# Laser_Teensy_proto.net
KiCad netlist of a schematic drawn in EAGLE
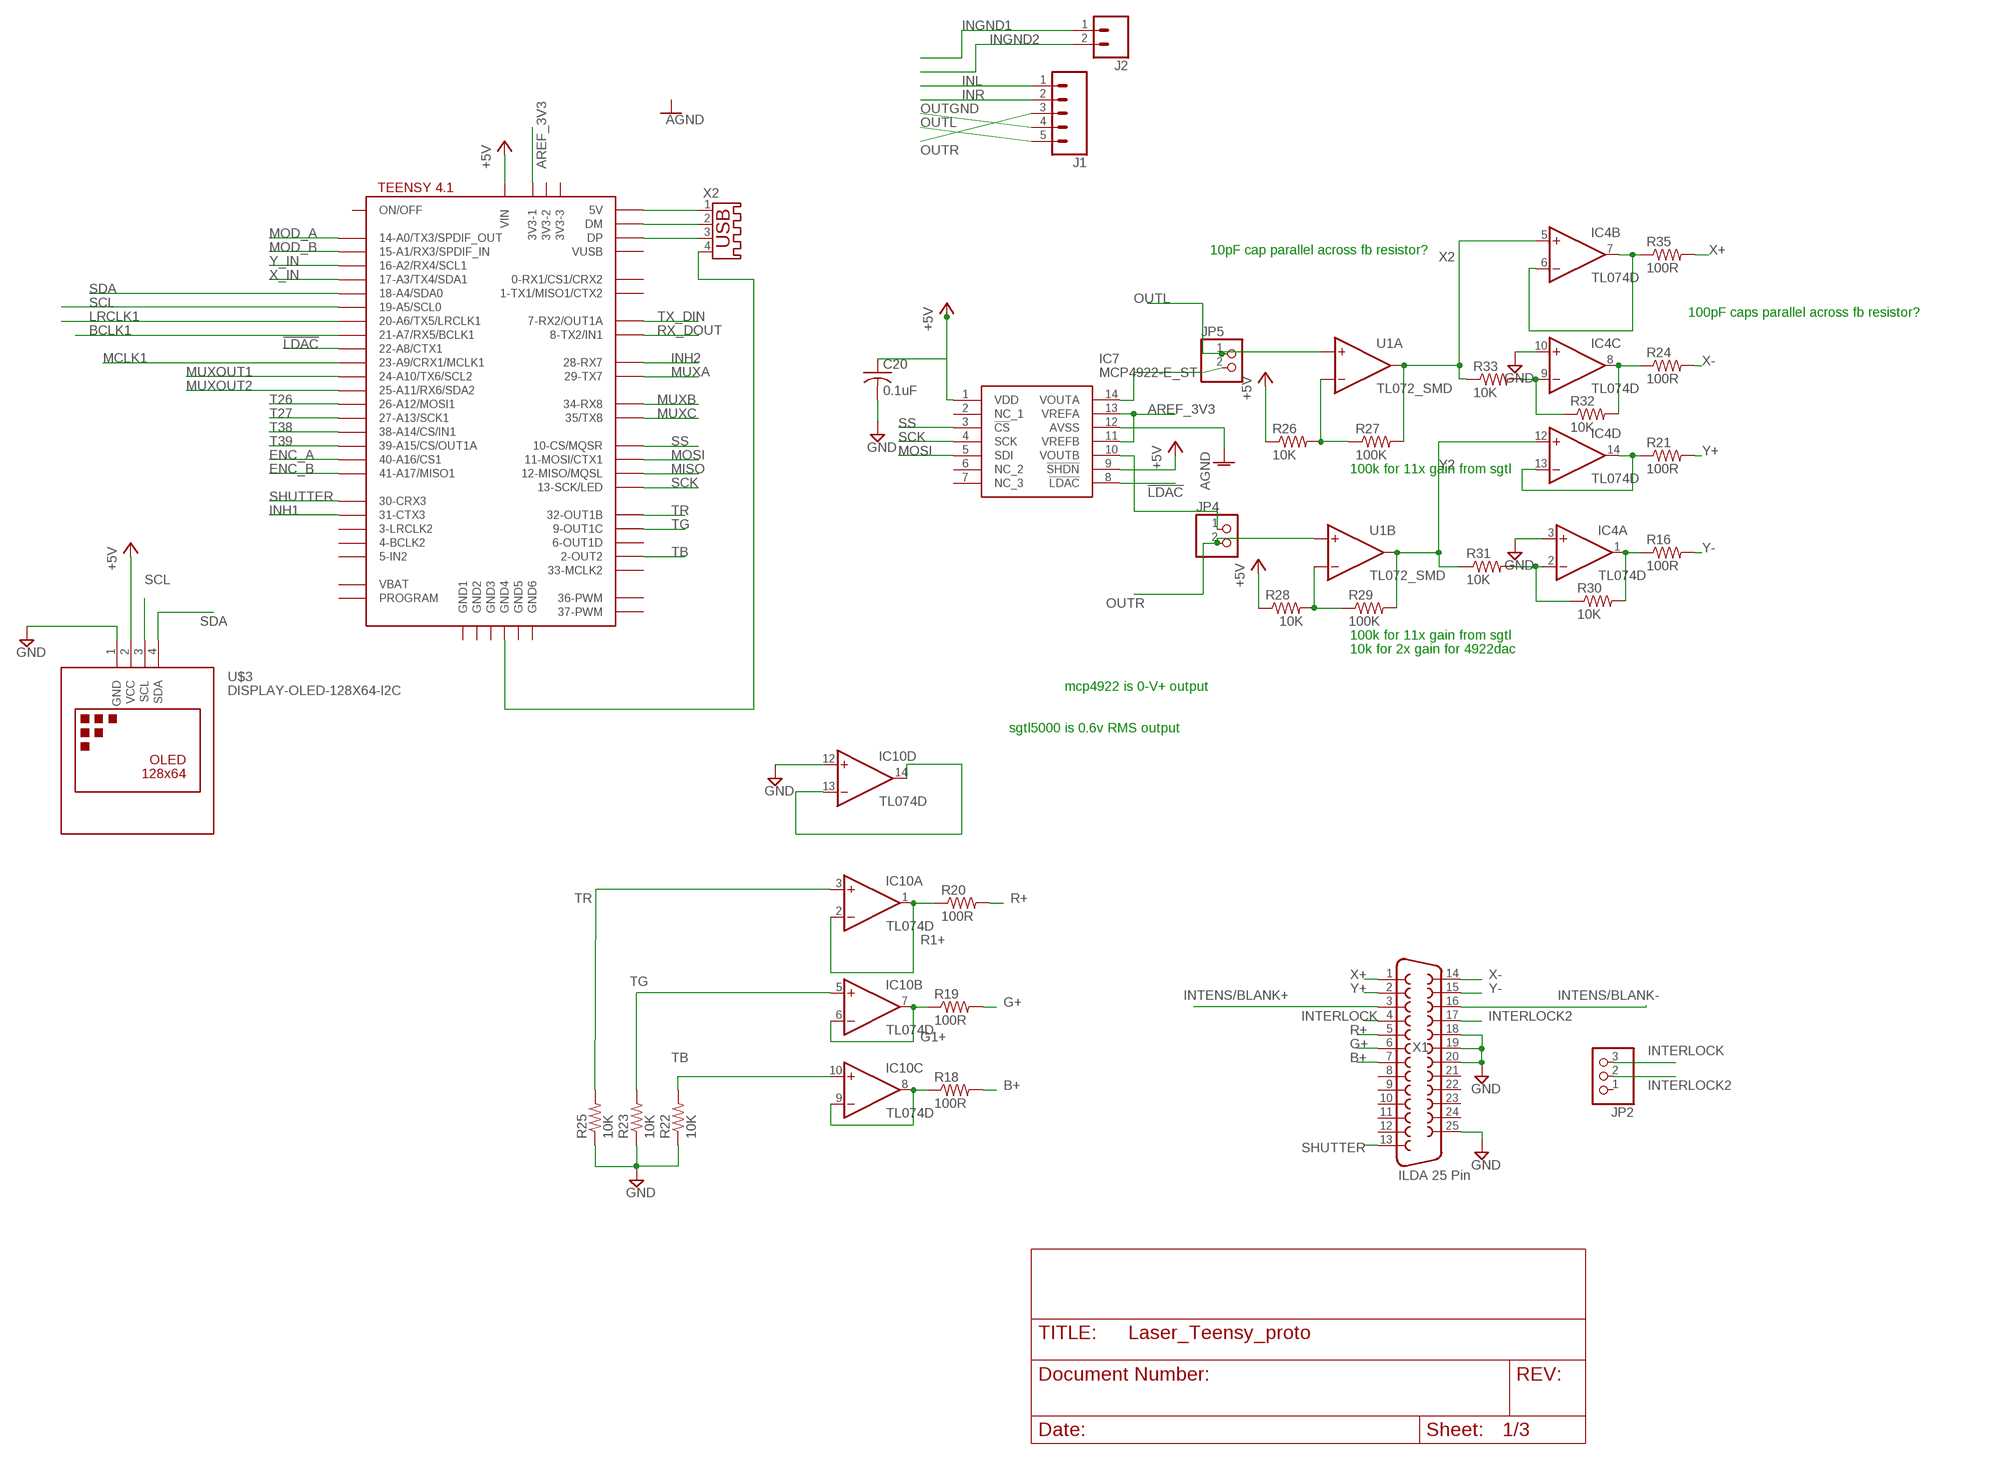
[diagram p0: schematic, sheet 1]
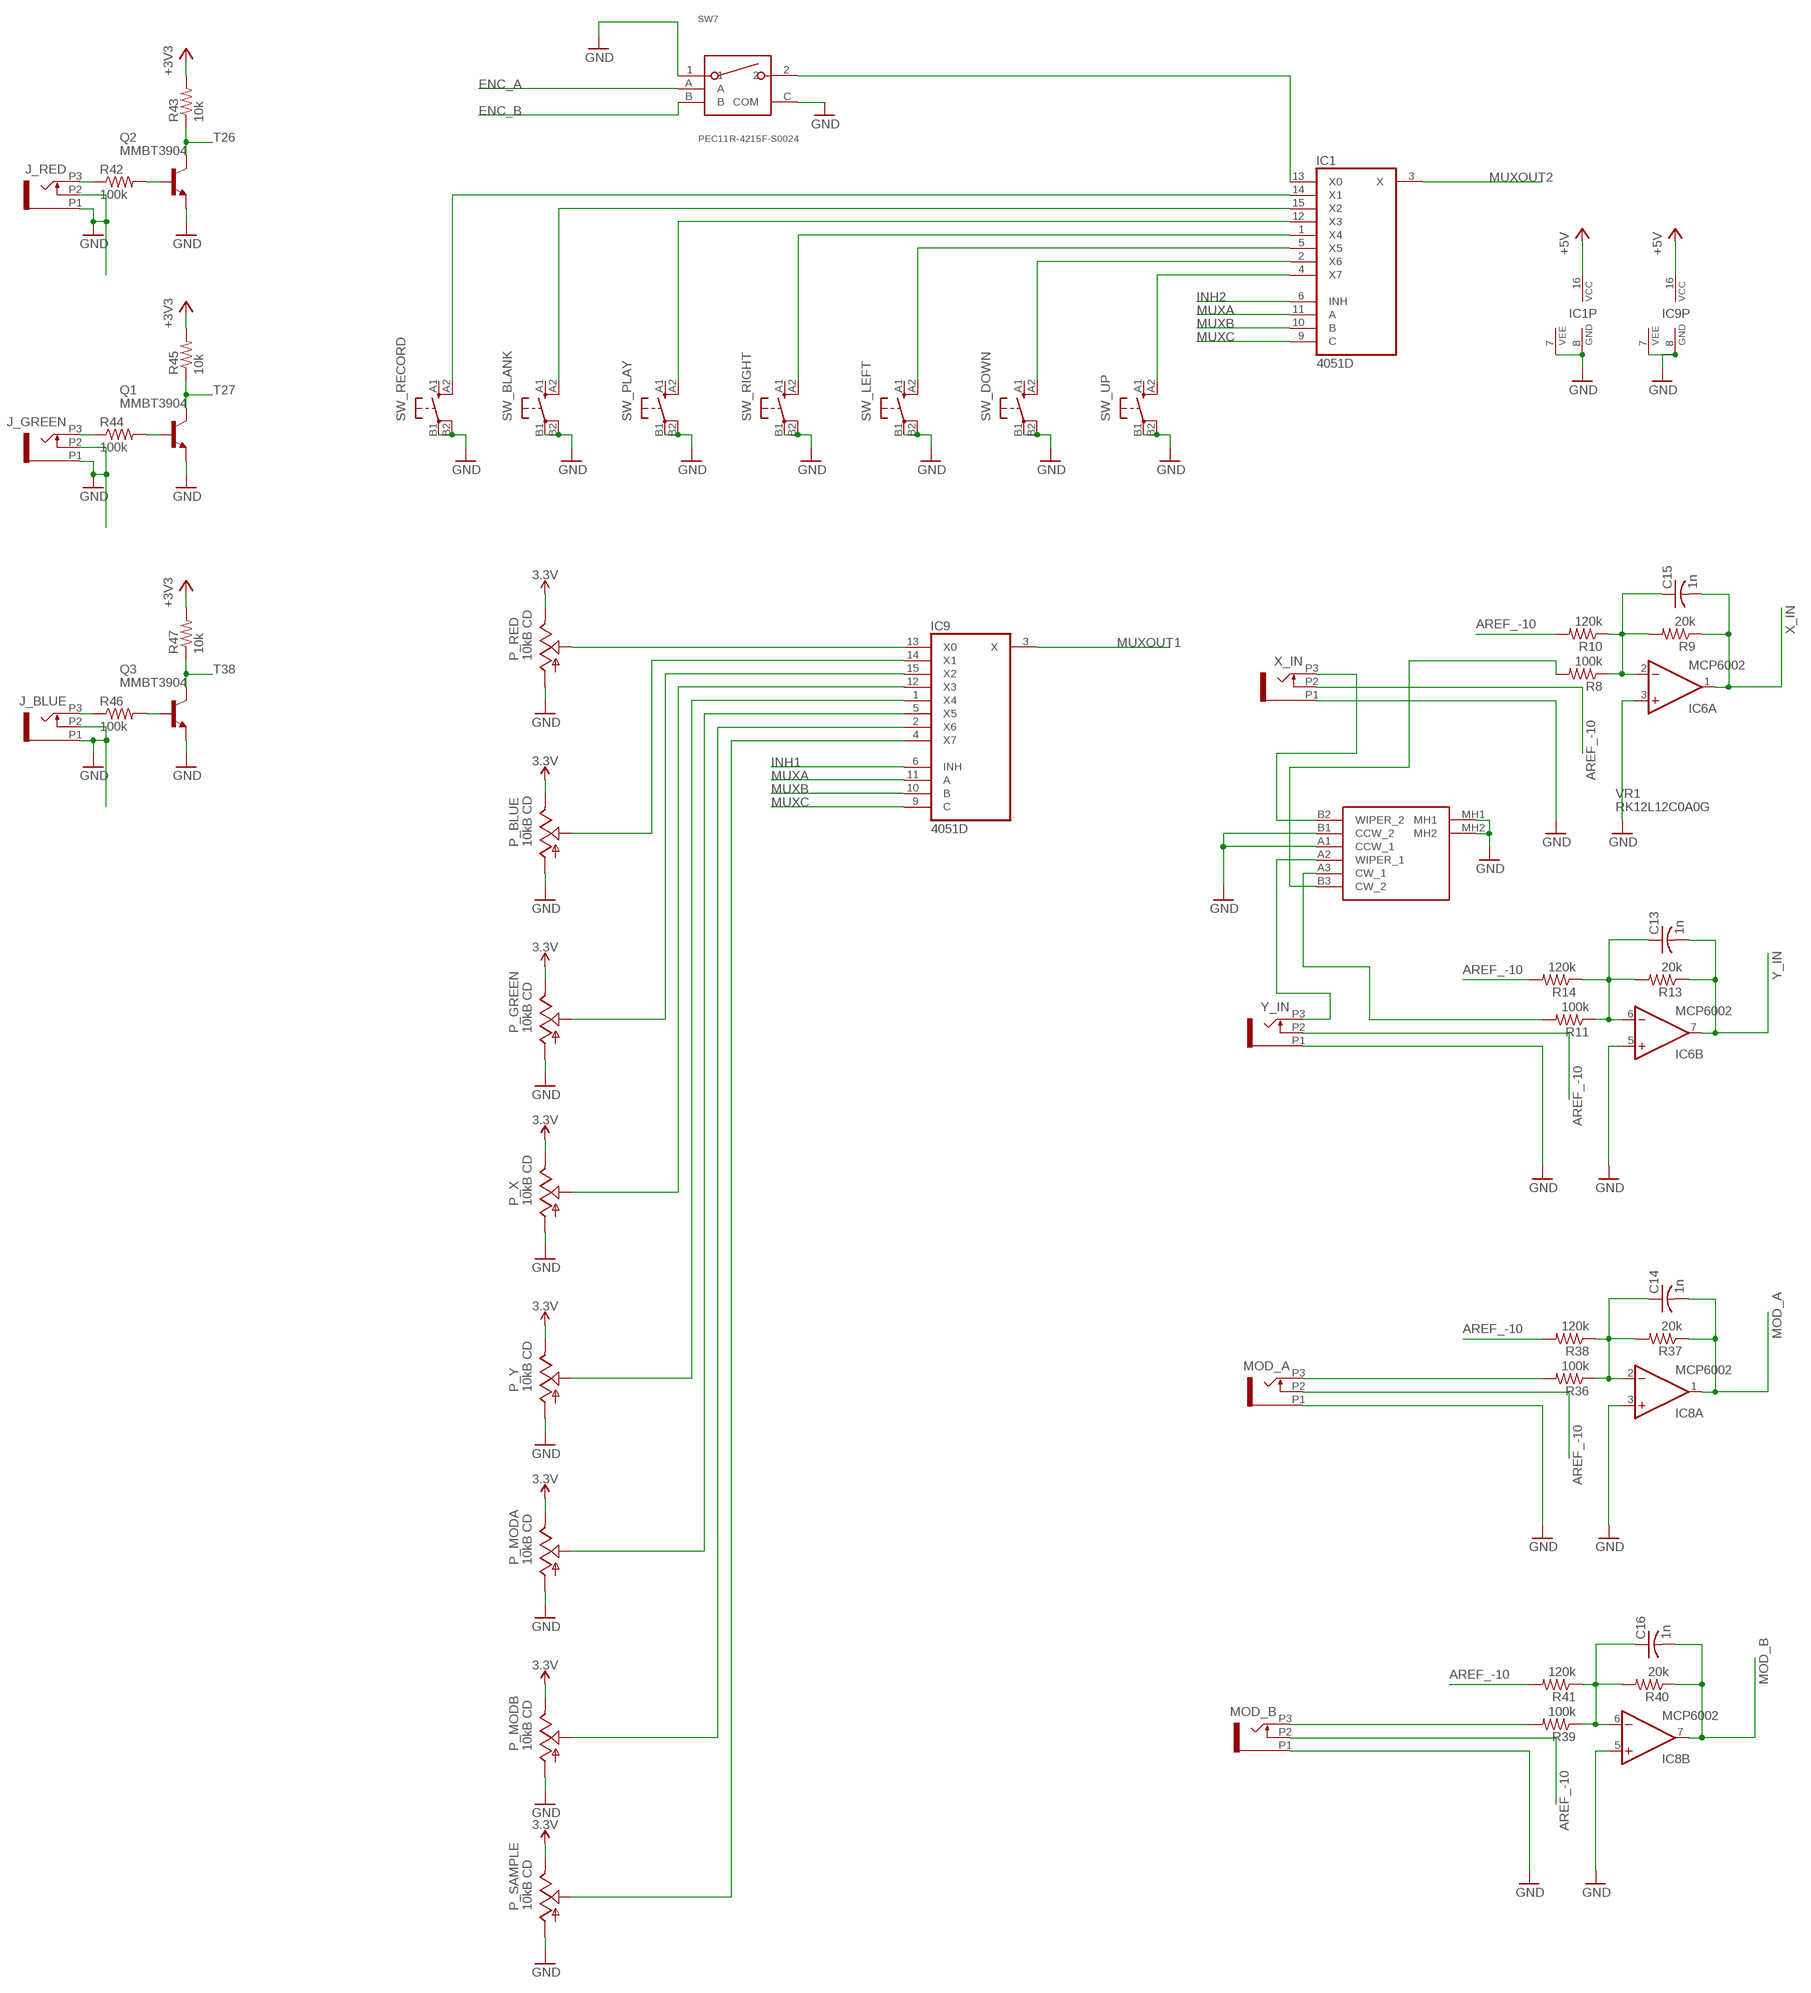
[diagram p1: schematic, sheet 2]
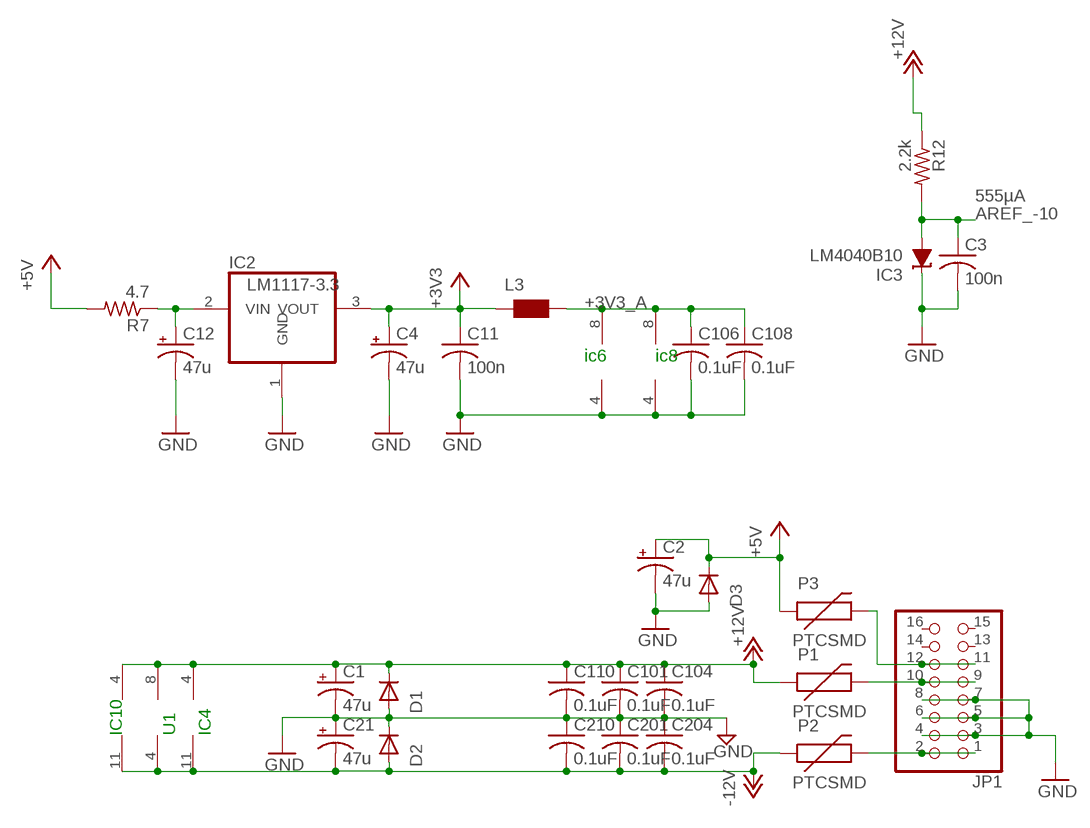
[diagram p2: schematic, sheet 3]

(export (version "E")
  (design (tool "Eeschema 10.0.6"))
  (components
    (comp (ref "C13")
      (value "1n")
      (footprint "eagle-import:C050-025X075")
      (libsource (lib "eagle-import") (part "rcl_334_C-US050-025X075"))
    )
    (comp (ref "C14")
      (value "1n")
      (footprint "eagle-import:C050-025X075")
      (libsource (lib "eagle-import") (part "rcl_334_C-US050-025X075"))
    )
    (comp (ref "C15")
      (value "1n")
      (footprint "eagle-import:C050-025X075")
      (libsource (lib "eagle-import") (part "rcl_334_C-US050-025X075"))
    )
    (comp (ref "C16")
      (value "1n")
      (footprint "eagle-import:C050-025X075")
      (libsource (lib "eagle-import") (part "rcl_334_C-US050-025X075"))
    )
    (comp (ref "IC1")
      (value "4051D")
      (footprint "eagle-import:SO16")
      (libsource (lib "eagle-import") (part "4051D"))
    )
    (comp (ref "IC6")
      (value "MCP6002")
      (footprint "eagle-import:SO08")
      (libsource (lib "eagle-import") (part "TL072D"))
    )
    (comp (ref "IC8")
      (value "MCP6002")
      (footprint "eagle-import:SO08")
      (libsource (lib "eagle-import") (part "TL072D"))
    )
    (comp (ref "IC9")
      (value "4051D")
      (footprint "eagle-import:SO16")
      (libsource (lib "eagle-import") (part "4051D"))
    )
    (comp (ref "J_BLUE")
      (value "PJ301_THONKICONN6")
      (footprint "eagle-import:WQP_PJ_301M6")
      (libsource (lib "eagle-import") (part "PJ301_THONKICONN6"))
    )
    (comp (ref "J_GREEN")
      (value "PJ301_THONKICONN6")
      (footprint "eagle-import:WQP_PJ_301M6")
      (libsource (lib "eagle-import") (part "PJ301_THONKICONN6"))
    )
    (comp (ref "J_RED")
      (value "PJ301_THONKICONN6")
      (footprint "eagle-import:WQP_PJ_301M6")
      (libsource (lib "eagle-import") (part "PJ301_THONKICONN6"))
    )
    (comp (ref "MOD_A")
      (value "PJ301_THONKICONN6")
      (footprint "eagle-import:WQP_PJ_301M6")
      (libsource (lib "eagle-import") (part "og-pj301_variations_PJ301_THONKICONN6"))
    )
    (comp (ref "MOD_B")
      (value "PJ301_THONKICONN6")
      (footprint "eagle-import:WQP_PJ_301M6")
      (libsource (lib "eagle-import") (part "og-pj301_variations_PJ301_THONKICONN6"))
    )
    (comp (ref "P_BLUE")
      (value "10kB CD")
      (footprint "eagle-import:ALPS_POT_VERTICAL_PS")
      (libsource (lib "eagle-import") (part "POT_USVERTICAL_PS"))
    )
    (comp (ref "P_GREEN")
      (value "10kB CD")
      (footprint "eagle-import:ALPS_POT_VERTICAL_PS")
      (libsource (lib "eagle-import") (part "POT_USVERTICAL_PS"))
    )
    (comp (ref "P_MODA")
      (value "10kB CD")
      (footprint "eagle-import:ALPS_POT_VERTICAL_PS")
      (libsource (lib "eagle-import") (part "POT_USVERTICAL_PS"))
    )
    (comp (ref "P_MODB")
      (value "10kB CD")
      (footprint "eagle-import:ALPS_POT_VERTICAL_PS")
      (libsource (lib "eagle-import") (part "POT_USVERTICAL_PS"))
    )
    (comp (ref "P_RED")
      (value "10kB CD")
      (footprint "eagle-import:ALPS_POT_VERTICAL_PS")
      (libsource (lib "eagle-import") (part "POT_USVERTICAL_PS"))
    )
    (comp (ref "P_SAMPLE")
      (value "10kB CD")
      (footprint "eagle-import:ALPS_POT_VERTICAL_PS")
      (libsource (lib "eagle-import") (part "POT_USVERTICAL_PS"))
    )
    (comp (ref "P_X")
      (value "10kB CD")
      (footprint "eagle-import:ALPS_POT_VERTICAL_PS")
      (libsource (lib "eagle-import") (part "POT_USVERTICAL_PS"))
    )
    (comp (ref "P_Y")
      (value "10kB CD")
      (footprint "eagle-import:ALPS_POT_VERTICAL_PS")
      (libsource (lib "eagle-import") (part "POT_USVERTICAL_PS"))
    )
    (comp (ref "Q1")
      (value "MMBT3904")
      (footprint "eagle-import:SOT23-BEC")
      (libsource (lib "eagle-import") (part "-NPN-SOT23-BECMMBT3904LT1"))
    )
    (comp (ref "Q2")
      (value "MMBT3904")
      (footprint "eagle-import:SOT23-BEC")
      (libsource (lib "eagle-import") (part "-NPN-SOT23-BECMMBT3904LT1"))
    )
    (comp (ref "Q3")
      (value "MMBT3904")
      (footprint "eagle-import:SOT23-BEC")
      (libsource (lib "eagle-import") (part "-NPN-SOT23-BECMMBT3904LT1"))
    )
    (comp (ref "R8")
      (value "100k")
      (footprint "eagle-import:0204_5")
      (libsource (lib "eagle-import") (part "rcl_334_R-US_0204/5"))
    )
    (comp (ref "R9")
      (value "20k")
      (footprint "eagle-import:0204_5")
      (libsource (lib "eagle-import") (part "rcl_334_R-US_0204/5"))
    )
    (comp (ref "R10")
      (value "120k")
      (footprint "eagle-import:0204_5")
      (libsource (lib "eagle-import") (part "rcl_334_R-US_0204/5"))
    )
    (comp (ref "R11")
      (value "100k")
      (footprint "eagle-import:0204_5")
      (libsource (lib "eagle-import") (part "rcl_334_R-US_0204/5"))
    )
    (comp (ref "R13")
      (value "20k")
      (footprint "eagle-import:0204_5")
      (libsource (lib "eagle-import") (part "rcl_334_R-US_0204/5"))
    )
    (comp (ref "R14")
      (value "120k")
      (footprint "eagle-import:0204_5")
      (libsource (lib "eagle-import") (part "rcl_334_R-US_0204/5"))
    )
    (comp (ref "R36")
      (value "100k")
      (footprint "eagle-import:0204_5")
      (libsource (lib "eagle-import") (part "rcl_334_R-US_0204/5"))
    )
    (comp (ref "R37")
      (value "20k")
      (footprint "eagle-import:0204_5")
      (libsource (lib "eagle-import") (part "rcl_334_R-US_0204/5"))
    )
    (comp (ref "R38")
      (value "120k")
      (footprint "eagle-import:0204_5")
      (libsource (lib "eagle-import") (part "rcl_334_R-US_0204/5"))
    )
    (comp (ref "R39")
      (value "100k")
      (footprint "eagle-import:0204_5")
      (libsource (lib "eagle-import") (part "rcl_334_R-US_0204/5"))
    )
    (comp (ref "R40")
      (value "20k")
      (footprint "eagle-import:0204_5")
      (libsource (lib "eagle-import") (part "rcl_334_R-US_0204/5"))
    )
    (comp (ref "R41")
      (value "120k")
      (footprint "eagle-import:0204_5")
      (libsource (lib "eagle-import") (part "rcl_334_R-US_0204/5"))
    )
    (comp (ref "R42")
      (value "100k")
      (footprint "eagle-import:0204_5")
      (libsource (lib "eagle-import") (part "rcl_334_R-US_0204/5"))
    )
    (comp (ref "R43")
      (value "10k")
      (footprint "eagle-import:0204_5")
      (libsource (lib "eagle-import") (part "rcl_334_R-US_0204/5"))
    )
    (comp (ref "R44")
      (value "100k")
      (footprint "eagle-import:0204_5")
      (libsource (lib "eagle-import") (part "rcl_334_R-US_0204/5"))
    )
    (comp (ref "R45")
      (value "10k")
      (footprint "eagle-import:0204_5")
      (libsource (lib "eagle-import") (part "rcl_334_R-US_0204/5"))
    )
    (comp (ref "R46")
      (value "100k")
      (footprint "eagle-import:0204_5")
      (libsource (lib "eagle-import") (part "rcl_334_R-US_0204/5"))
    )
    (comp (ref "R47")
      (value "10k")
      (footprint "eagle-import:0204_5")
      (libsource (lib "eagle-import") (part "rcl_334_R-US_0204/5"))
    )
    (comp (ref "SW7")
      (value "PEC11R-4215F-S0024")
      (footprint "eagle-import:PEC11R-4215F-S0024")
      (fields
        (field (name "DIGIKEY_PART_NUMBER") "PEC11R-4215F-S0024-ND")
        (field (name "MANUFACTURER") "Bourns Inc.")
        (field (name "CREATED_BY") "PCBLayout.com")
      )
      (libsource (lib "eagle-import") (part "PEC11R-4215F-S0024"))
    )
    (comp (ref "SW_BLANK")
      (value "D6R")
      (footprint "eagle-import:D6R")
      (libsource (lib "eagle-import") (part "D6R"))
    )
    (comp (ref "SW_DOWN")
      (value "D6R")
      (footprint "eagle-import:D6R")
      (libsource (lib "eagle-import") (part "D6R"))
    )
    (comp (ref "SW_LEFT")
      (value "D6R")
      (footprint "eagle-import:D6R")
      (libsource (lib "eagle-import") (part "D6R"))
    )
    (comp (ref "SW_PLAY")
      (value "D6R")
      (footprint "eagle-import:D6R")
      (libsource (lib "eagle-import") (part "D6R"))
    )
    (comp (ref "SW_RECORD")
      (value "D6R")
      (footprint "eagle-import:D6R")
      (libsource (lib "eagle-import") (part "D6R"))
    )
    (comp (ref "SW_RIGHT")
      (value "D6R")
      (footprint "eagle-import:D6R")
      (libsource (lib "eagle-import") (part "D6R"))
    )
    (comp (ref "SW_UP")
      (value "D6R")
      (footprint "eagle-import:D6R")
      (libsource (lib "eagle-import") (part "D6R"))
    )
    (comp (ref "VR1")
      (value "RK12L12C0A0G")
      (footprint "eagle-import:RK12L12C0A0G")
      (fields (field (name "MOUSER_PART_NUMBER") "688-RK12L12C0A0G"))
      (libsource (lib "eagle-import") (part "RK12L12C0A0G"))
    )
    (comp (ref "X_IN")
      (value "PJ301_THONKICONN6")
      (footprint "eagle-import:WQP_PJ_301M6")
      (libsource (lib "eagle-import") (part "og-pj301_variations_PJ301_THONKICONN6"))
    )
    (comp (ref "Y_IN")
      (value "PJ301_THONKICONN6")
      (footprint "eagle-import:WQP_PJ_301M6")
      (libsource (lib "eagle-import") (part "og-pj301_variations_PJ301_THONKICONN6"))
    )
    (comp (ref "C1")
      (value "47u")
      (footprint "eagle-import:E3,5-8")
      (libsource (lib "eagle-import") (part "CPOL-USE3.5-8"))
    )
    (comp (ref "C2")
      (value "47u")
      (footprint "eagle-import:E3,5-8")
      (libsource (lib "eagle-import") (part "CPOL-USE3.5-8"))
    )
    (comp (ref "C3")
      (value "100n")
      (footprint "eagle-import:C0603")
      (libsource (lib "eagle-import") (part "rcl_C-USC0603"))
    )
    (comp (ref "C4")
      (value "47u")
      (footprint "eagle-import:E3,5-8")
      (libsource (lib "eagle-import") (part "CPOL-USE3.5-8"))
    )
    (comp (ref "C11")
      (value "100n")
      (footprint "eagle-import:C0603")
      (libsource (lib "eagle-import") (part "rcl_C-USC0603"))
    )
    (comp (ref "C12")
      (value "47u")
      (footprint "eagle-import:E3,5-8")
      (libsource (lib "eagle-import") (part "CPOL-USE3.5-8"))
    )
    (comp (ref "C21")
      (value "47u")
      (footprint "eagle-import:E3,5-8")
      (libsource (lib "eagle-import") (part "CPOL-USE3.5-8"))
    )
    (comp (ref "C101")
      (value "0.1uF")
      (footprint "eagle-import:C0603")
      (libsource (lib "eagle-import") (part "C-USC0603"))
    )
    (comp (ref "C104")
      (value "0.1uF")
      (footprint "eagle-import:C0603")
      (libsource (lib "eagle-import") (part "C-USC0603"))
    )
    (comp (ref "C106")
      (value "0.1uF")
      (footprint "eagle-import:C0603")
      (libsource (lib "eagle-import") (part "C-USC0603"))
    )
    (comp (ref "C108")
      (value "0.1uF")
      (footprint "eagle-import:C0603")
      (libsource (lib "eagle-import") (part "C-USC0603"))
    )
    (comp (ref "C110")
      (value "0.1uF")
      (footprint "eagle-import:C0603")
      (libsource (lib "eagle-import") (part "C-USC0603"))
    )
    (comp (ref "C201")
      (value "0.1uF")
      (footprint "eagle-import:C0603")
      (libsource (lib "eagle-import") (part "C-USC0603"))
    )
    (comp (ref "C204")
      (value "0.1uF")
      (footprint "eagle-import:C0603")
      (libsource (lib "eagle-import") (part "C-USC0603"))
    )
    (comp (ref "C210")
      (value "0.1uF")
      (footprint "eagle-import:C0603")
      (libsource (lib "eagle-import") (part "C-USC0603"))
    )
    (comp (ref "D1")
      (value "1N5819HW")
      (footprint "eagle-import:SOD123")
      (libsource (lib "eagle-import") (part "DIODE-SOD123"))
    )
    (comp (ref "D2")
      (value "1N5819HW")
      (footprint "eagle-import:SOD123")
      (libsource (lib "eagle-import") (part "DIODE-SOD123"))
    )
    (comp (ref "D3")
      (value "1N5819HW")
      (footprint "eagle-import:SOD123")
      (libsource (lib "eagle-import") (part "DIODE-SOD123"))
    )
    (comp (ref "IC2")
      (value "LM1117-3.3")
      (footprint "eagle-import:TO252")
      (libsource (lib "eagle-import") (part "REG1117T"))
    )
    (comp (ref "IC3")
      (value "LM4040B10")
      (footprint "eagle-import:DBZ_R-PDSO-G3")
      (libsource (lib "eagle-import") (part "LM4041DBZB12"))
    )
    (comp (ref "IC4")
      (value "TL074D")
      (footprint "eagle-import:SO14")
      (libsource (lib "eagle-import") (part "TL074D"))
    )
    (comp (ref "IC10")
      (value "TL074D")
      (footprint "eagle-import:SO14")
      (libsource (lib "eagle-import") (part "TL074D"))
    )
    (comp (ref "JP1")
      (value "PINHD-2X8")
      (footprint "eagle-import:2X08")
      (libsource (lib "eagle-import") (part "PINHD-2X8"))
    )
    (comp (ref "L3")
      (value "WE-CBF_0603")
      (footprint "eagle-import:0603")
      (libsource (lib "eagle-import") (part "WE-CBF_0603"))
    )
    (comp (ref "P1")
      (value "PTCSMD")
      (footprint "eagle-import:PTC-1206")
      (libsource (lib "eagle-import") (part "PTCSMD"))
    )
    (comp (ref "P2")
      (value "PTCSMD")
      (footprint "eagle-import:PTC-1206")
      (libsource (lib "eagle-import") (part "PTCSMD"))
    )
    (comp (ref "P3")
      (value "PTCSMD")
      (footprint "eagle-import:PTC-1206")
      (libsource (lib "eagle-import") (part "PTCSMD"))
    )
    (comp (ref "R7")
      (value "4.7")
      (footprint "eagle-import:R1206")
      (libsource (lib "eagle-import") (part "R-US_R1206"))
    )
    (comp (ref "R12")
      (value "2.2k")
      (footprint "eagle-import:0204_5")
      (libsource (lib "eagle-import") (part "rcl_334_R-US_0204/5"))
    )
    (comp (ref "U1")
      (value "TL072_SMD")
      (footprint "eagle-import:SO08")
      (libsource (lib "eagle-import") (part "TL072_SMD"))
    )
    (comp (ref "C20")
      (value "0.1uF")
      (footprint "eagle-import:C0603")
      (libsource (lib "eagle-import") (part "C-USC0603"))
    )
    (comp (ref "IC7")
      (value "MCP4922-E_ST")
      (footprint "eagle-import:SOP65P638X110-14N")
      (fields
        (field (name "ARROW_PART_NUMBER") "MCP4922-E/ST")
        (field (name "MOUSER_PART_NUMBER") "579-MCP4922-E/ST")
      )
      (libsource (lib "eagle-import") (part "MCP4922-E_ST"))
    )
    (comp (ref "J1")
      (value "CONN_05")
      (footprint "eagle-import:1X05")
      (libsource (lib "eagle-import") (part "CONN_05"))
    )
    (comp (ref "J2")
      (value "CONN_02")
      (footprint "eagle-import:1X02")
      (libsource (lib "eagle-import") (part "CONN_02"))
    )
    (comp (ref "JP2")
      (value "PINHD-1X3")
      (footprint "eagle-import:1X03")
      (libsource (lib "eagle-import") (part "PINHD-1X3"))
    )
    (comp (ref "JP4")
      (value "PINHD-1X2")
      (footprint "eagle-import:1X02")
      (libsource (lib "eagle-import") (part "PINHD-1X2"))
    )
    (comp (ref "JP5")
      (value "PINHD-1X2")
      (footprint "eagle-import:1X02")
      (libsource (lib "eagle-import") (part "PINHD-1X2"))
    )
    (comp (ref "R16")
      (value "100R")
      (footprint "eagle-import:0204_5")
      (libsource (lib "eagle-import") (part "rcl_334_R-US_0204/5"))
    )
    (comp (ref "R18")
      (value "100R")
      (footprint "eagle-import:0204_5")
      (libsource (lib "eagle-import") (part "rcl_334_R-US_0204/5"))
    )
    (comp (ref "R19")
      (value "100R")
      (footprint "eagle-import:0204_5")
      (libsource (lib "eagle-import") (part "rcl_334_R-US_0204/5"))
    )
    (comp (ref "R20")
      (value "100R")
      (footprint "eagle-import:0204_5")
      (libsource (lib "eagle-import") (part "rcl_334_R-US_0204/5"))
    )
    (comp (ref "R21")
      (value "100R")
      (footprint "eagle-import:0204_5")
      (libsource (lib "eagle-import") (part "rcl_334_R-US_0204/5"))
    )
    (comp (ref "R22")
      (value "10K")
      (footprint "eagle-import:0204_5")
      (libsource (lib "eagle-import") (part "rcl_334_R-US_0204/5"))
    )
    (comp (ref "R23")
      (value "10K")
      (footprint "eagle-import:0204_5")
      (libsource (lib "eagle-import") (part "rcl_334_R-US_0204/5"))
    )
    (comp (ref "R24")
      (value "100R")
      (footprint "eagle-import:0204_5")
      (libsource (lib "eagle-import") (part "rcl_334_R-US_0204/5"))
    )
    (comp (ref "R25")
      (value "10K")
      (footprint "eagle-import:0204_5")
      (libsource (lib "eagle-import") (part "rcl_334_R-US_0204/5"))
    )
    (comp (ref "R26")
      (value "10K")
      (footprint "eagle-import:0204_5")
      (libsource (lib "eagle-import") (part "rcl_334_R-US_0204/5"))
    )
    (comp (ref "R27")
      (value "100K")
      (footprint "eagle-import:0204_5")
      (libsource (lib "eagle-import") (part "rcl_334_R-US_0204/5"))
    )
    (comp (ref "R28")
      (value "10K")
      (footprint "eagle-import:0204_5")
      (libsource (lib "eagle-import") (part "rcl_334_R-US_0204/5"))
    )
    (comp (ref "R29")
      (value "100K")
      (footprint "eagle-import:0204_5")
      (libsource (lib "eagle-import") (part "rcl_334_R-US_0204/5"))
    )
    (comp (ref "R30")
      (value "10K")
      (footprint "eagle-import:0204_5")
      (libsource (lib "eagle-import") (part "rcl_334_R-US_0204/5"))
    )
    (comp (ref "R31")
      (value "10K")
      (footprint "eagle-import:0204_5")
      (libsource (lib "eagle-import") (part "rcl_334_R-US_0204/5"))
    )
    (comp (ref "R32")
      (value "10K")
      (footprint "eagle-import:R0603")
      (libsource (lib "eagle-import") (part "resistor_R-US_R0603"))
    )
    (comp (ref "R33")
      (value "10K")
      (footprint "eagle-import:0204_5")
      (libsource (lib "eagle-import") (part "rcl_334_R-US_0204/5"))
    )
    (comp (ref "R35")
      (value "100R")
      (footprint "eagle-import:0204_5")
      (libsource (lib "eagle-import") (part "rcl_334_R-US_0204/5"))
    )
    (comp (ref "U$2")
      (value "TEENSY41-E")
      (footprint "eagle-import:TENNSY41-E")
      (libsource (lib "eagle-import") (part "TEENSY41-E"))
    )
    (comp (ref "U$3")
      (value "DISPLAY-OLED-128X64-I2C")
      (footprint "eagle-import:DISPLAY-OLED-128X64-I2C")
      (libsource (lib "eagle-import") (part "DISPLAY-OLED-128X64-I2C"))
    )
    (comp (ref "X1")
      (value "ILDA 25 Pin")
      (footprint "eagle-import:F25D")
      (libsource (lib "eagle-import") (part "F25D"))
    )
    (comp (ref "X2")
      (value "USB-A003")
      (footprint "eagle-import:USB-A003")
      (libsource (lib "eagle-import") (part "USB-A003"))
    )
  )
  (nets
    (net (code "1") (name "+3V3") (class "Default")
      (node (ref "C11") (pin "1") (pinfunction "1_1") (pintype "passive"))
      (node (ref "C4") (pin "+") (pinfunction "+_+") (pintype "passive"))
      (node (ref "IC2") (pin "3") (pinfunction "VOUT_3") (pintype "output"))
      (node (ref "L3") (pin "1") (pinfunction "1_1") (pintype "passive"))
      (node (ref "R43") (pin "2") (pinfunction "2_2") (pintype "passive"))
      (node (ref "R45") (pin "2") (pinfunction "2_2") (pintype "passive"))
      (node (ref "R47") (pin "2") (pinfunction "2_2") (pintype "passive"))
    )
    (net (code "2") (name "+3V3_A") (class "Default")
      (node (ref "C106") (pin "1") (pinfunction "1_1") (pintype "passive"))
      (node (ref "C108") (pin "1") (pinfunction "1_1") (pintype "passive"))
      (node (ref "IC6") (pin "8") (pinfunction "V+_8") (pintype "power_in"))
      (node (ref "IC8") (pin "8") (pinfunction "V+_8") (pintype "power_in"))
      (node (ref "L3") (pin "2") (pinfunction "2_2") (pintype "passive"))
    )
    (net (code "3") (name "+5V") (class "Default")
      (node (ref "C2") (pin "+") (pinfunction "+_+") (pintype "passive"))
      (node (ref "C20") (pin "1") (pinfunction "1_1") (pintype "passive"))
      (node (ref "D3") (pin "C") (pinfunction "C_C") (pintype "passive"))
      (node (ref "IC1") (pin "16") (pinfunction "VCC_16") (pintype "power_in"))
      (node (ref "IC7") (pin "1") (pinfunction "VDD_1") (pintype "bidirectional"))
      (node (ref "IC7") (pin "9") (pinfunction "~{SHDN}_9") (pintype "bidirectional"))
      (node (ref "IC9") (pin "16") (pinfunction "VCC_16") (pintype "power_in"))
      (node (ref "P3") (pin "1") (pinfunction "1_1") (pintype "bidirectional"))
      (node (ref "R26") (pin "1") (pinfunction "1_1") (pintype "passive"))
      (node (ref "R28") (pin "1") (pinfunction "1_1") (pintype "passive"))
      (node (ref "R7") (pin "2") (pinfunction "2_2") (pintype "passive"))
      (node (ref "U$2") (pin "VIN") (pinfunction "VIN_VIN") (pintype "bidirectional"))
      (node (ref "U$3") (pin "2") (pinfunction "VCC_2") (pintype "power_in"))
    )
    (net (code "4") (name "+12V") (class "Default")
      (node (ref "C1") (pin "+") (pinfunction "+_+") (pintype "passive"))
      (node (ref "C101") (pin "1") (pinfunction "1_1") (pintype "passive"))
      (node (ref "C104") (pin "1") (pinfunction "1_1") (pintype "passive"))
      (node (ref "C110") (pin "1") (pinfunction "1_1") (pintype "passive"))
      (node (ref "D1") (pin "C") (pinfunction "C_C") (pintype "passive"))
      (node (ref "IC10") (pin "4") (pinfunction "V+_4") (pintype "power_in"))
      (node (ref "IC4") (pin "4") (pinfunction "V+_4") (pintype "power_in"))
      (node (ref "P1") (pin "1") (pinfunction "1_1") (pintype "bidirectional"))
      (node (ref "R12") (pin "1") (pinfunction "1_1") (pintype "passive"))
      (node (ref "U1") (pin "8") (pinfunction "V+_8") (pintype "power_in"))
    )
    (net (code "5") (name "-12V") (class "Default")
      (node (ref "C201") (pin "2") (pinfunction "2_2") (pintype "passive"))
      (node (ref "C204") (pin "2") (pinfunction "2_2") (pintype "passive"))
      (node (ref "C21") (pin "-") (pinfunction "-_-") (pintype "passive"))
      (node (ref "C210") (pin "2") (pinfunction "2_2") (pintype "passive"))
      (node (ref "D2") (pin "A") (pinfunction "A_A") (pintype "passive"))
      (node (ref "IC10") (pin "11") (pinfunction "V-_11") (pintype "power_in"))
      (node (ref "IC4") (pin "11") (pinfunction "V-_11") (pintype "power_in"))
      (node (ref "P2") (pin "1") (pinfunction "1_1") (pintype "bidirectional"))
      (node (ref "U1") (pin "4") (pinfunction "V-_4") (pintype "power_in"))
    )
    (net (code "6") (name "3.3V") (class "Default")
      (node (ref "P_BLUE") (pin "P$1") (pinfunction "E_P$1") (pintype "passive"))
      (node (ref "P_GREEN") (pin "P$1") (pinfunction "E_P$1") (pintype "passive"))
      (node (ref "P_MODA") (pin "P$1") (pinfunction "E_P$1") (pintype "passive"))
      (node (ref "P_MODB") (pin "P$1") (pinfunction "E_P$1") (pintype "passive"))
      (node (ref "P_RED") (pin "P$1") (pinfunction "E_P$1") (pintype "passive"))
      (node (ref "P_SAMPLE") (pin "P$1") (pinfunction "E_P$1") (pintype "passive"))
      (node (ref "P_X") (pin "P$1") (pinfunction "E_P$1") (pintype "passive"))
      (node (ref "P_Y") (pin "P$1") (pinfunction "E_P$1") (pintype "passive"))
    )
    (net (code "7") (name "AGND") (class "Default")
      (node (ref "IC7") (pin "12") (pinfunction "AVSS_12") (pintype "bidirectional"))
    )
    (net (code "8") (name "AREF_-10") (class "Default")
      (node (ref "C3") (pin "1") (pinfunction "1_1") (pintype "passive"))
      (node (ref "IC3") (pin "2") (pinfunction "A_2") (pintype "passive"))
      (node (ref "MOD_A") (pin "P2") (pinfunction "2_P2") (pintype "passive"))
      (node (ref "MOD_B") (pin "P2") (pinfunction "2_P2") (pintype "passive"))
      (node (ref "R10") (pin "2") (pinfunction "2_2") (pintype "passive"))
      (node (ref "R12") (pin "2") (pinfunction "2_2") (pintype "passive"))
      (node (ref "R14") (pin "2") (pinfunction "2_2") (pintype "passive"))
      (node (ref "R38") (pin "2") (pinfunction "2_2") (pintype "passive"))
      (node (ref "R41") (pin "2") (pinfunction "2_2") (pintype "passive"))
      (node (ref "X_IN") (pin "P2") (pinfunction "2_P2") (pintype "passive"))
      (node (ref "Y_IN") (pin "P2") (pinfunction "2_P2") (pintype "passive"))
    )
    (net (code "9") (name "AREF_3V3") (class "Default")
      (node (ref "IC7") (pin "11") (pinfunction "VREFB_11") (pintype "bidirectional"))
      (node (ref "IC7") (pin "13") (pinfunction "VREFA_13") (pintype "bidirectional"))
      (node (ref "U$2") (pin "3V3-1") (pinfunction "3V3-1_3V3-1") (pintype "bidirectional"))
    )
    (net (code "10") (name "B+") (class "Default")
      (node (ref "R18") (pin "2") (pinfunction "2_2") (pintype "passive"))
      (node (ref "X1") (pin "7") (pinfunction "7_7") (pintype "passive"))
    )
    (net (code "11") (name "BCLK1") (class "Default")
      (node (ref "U$2") (pin "21-A7/RX5/BCLK1") (pinfunction "21-A7/RX5/BCLK1_21-A7/RX5/BCLK1") (pintype "bidirectional"))
    )
    (net (code "12") (name "ENC_A") (class "Default")
      (node (ref "SW7") (pin "A") (pinfunction "A_A") (pintype "passive"))
      (node (ref "U$2") (pin "40-A16/CS1") (pinfunction "40-A16/CS1_40-A16/CS1") (pintype "bidirectional"))
    )
    (net (code "13") (name "ENC_B") (class "Default")
      (node (ref "SW7") (pin "B") (pinfunction "B_B") (pintype "passive"))
      (node (ref "U$2") (pin "41-A17/MISO1") (pinfunction "41-A17/MISO1_41-A17/MISO1") (pintype "bidirectional"))
    )
    (net (code "14") (name "G+") (class "Default")
      (node (ref "R19") (pin "2") (pinfunction "2_2") (pintype "passive"))
      (node (ref "X1") (pin "6") (pinfunction "6_6") (pintype "passive"))
    )
    (net (code "15") (name "G1+") (class "Default")
      (node (ref "IC10") (pin "6") (pinfunction "-IN_6") (pintype "input"))
      (node (ref "IC10") (pin "7") (pinfunction "OUT_7") (pintype "output"))
      (node (ref "R19") (pin "1") (pinfunction "1_1") (pintype "passive"))
    )
    (net (code "16") (name "GND") (class "Default")
      (node (ref "C1") (pin "-") (pinfunction "-_-") (pintype "passive"))
      (node (ref "C101") (pin "2") (pinfunction "2_2") (pintype "passive"))
      (node (ref "C104") (pin "2") (pinfunction "2_2") (pintype "passive"))
      (node (ref "C106") (pin "2") (pinfunction "2_2") (pintype "passive"))
      (node (ref "C108") (pin "2") (pinfunction "2_2") (pintype "passive"))
      (node (ref "C11") (pin "2") (pinfunction "2_2") (pintype "passive"))
      (node (ref "C110") (pin "2") (pinfunction "2_2") (pintype "passive"))
      (node (ref "C12") (pin "-") (pinfunction "-_-") (pintype "passive"))
      (node (ref "C2") (pin "-") (pinfunction "-_-") (pintype "passive"))
      (node (ref "C20") (pin "2") (pinfunction "2_2") (pintype "passive"))
      (node (ref "C201") (pin "1") (pinfunction "1_1") (pintype "passive"))
      (node (ref "C204") (pin "1") (pinfunction "1_1") (pintype "passive"))
      (node (ref "C21") (pin "+") (pinfunction "+_+") (pintype "passive"))
      (node (ref "C210") (pin "1") (pinfunction "1_1") (pintype "passive"))
      (node (ref "C3") (pin "2") (pinfunction "2_2") (pintype "passive"))
      (node (ref "C4") (pin "-") (pinfunction "-_-") (pintype "passive"))
      (node (ref "D1") (pin "A") (pinfunction "A_A") (pintype "passive"))
      (node (ref "D2") (pin "C") (pinfunction "C_C") (pintype "passive"))
      (node (ref "D3") (pin "A") (pinfunction "A_A") (pintype "passive"))
      (node (ref "IC1") (pin "7") (pinfunction "VEE_7") (pintype "power_in"))
      (node (ref "IC1") (pin "8") (pinfunction "GND_8") (pintype "power_in"))
      (node (ref "IC10") (pin "12") (pinfunction "+IN_12") (pintype "input"))
      (node (ref "IC2") (pin "1") (pinfunction "GND_1") (pintype "power_in"))
      (node (ref "IC3") (pin "1") (pinfunction "C_1") (pintype "passive"))
      (node (ref "IC4") (pin "10") (pinfunction "+IN_10") (pintype "input"))
      (node (ref "IC4") (pin "3") (pinfunction "+IN_3") (pintype "input"))
      (node (ref "IC6") (pin "3") (pinfunction "+IN_3") (pintype "input"))
      (node (ref "IC6") (pin "4") (pinfunction "V-_4") (pintype "power_in"))
      (node (ref "IC6") (pin "5") (pinfunction "+IN_5") (pintype "input"))
      (node (ref "IC8") (pin "3") (pinfunction "+IN_3") (pintype "input"))
      (node (ref "IC8") (pin "4") (pinfunction "V-_4") (pintype "power_in"))
      (node (ref "IC8") (pin "5") (pinfunction "+IN_5") (pintype "input"))
      (node (ref "IC9") (pin "7") (pinfunction "VEE_7") (pintype "power_in"))
      (node (ref "IC9") (pin "8") (pinfunction "GND_8") (pintype "power_in"))
      (node (ref "JP1") (pin "3") (pinfunction "3_3") (pintype "passive"))
      (node (ref "JP1") (pin "4") (pinfunction "4_4") (pintype "passive"))
      (node (ref "JP1") (pin "5") (pinfunction "5_5") (pintype "passive"))
      (node (ref "JP1") (pin "6") (pinfunction "6_6") (pintype "passive"))
      (node (ref "JP1") (pin "7") (pinfunction "7_7") (pintype "passive"))
      (node (ref "JP1") (pin "8") (pinfunction "8_8") (pintype "passive"))
      (node (ref "J_BLUE") (pin "P1") (pinfunction "1_P1") (pintype "passive"))
      (node (ref "J_BLUE") (pin "P2") (pinfunction "2_P2") (pintype "passive"))
      (node (ref "J_GREEN") (pin "P1") (pinfunction "1_P1") (pintype "passive"))
      (node (ref "J_GREEN") (pin "P2") (pinfunction "2_P2") (pintype "passive"))
      (node (ref "J_RED") (pin "P1") (pinfunction "1_P1") (pintype "passive"))
      (node (ref "J_RED") (pin "P2") (pinfunction "2_P2") (pintype "passive"))
      (node (ref "MOD_A") (pin "P1") (pinfunction "1_P1") (pintype "passive"))
      (node (ref "MOD_B") (pin "P1") (pinfunction "1_P1") (pintype "passive"))
      (node (ref "P_BLUE") (pin "P$3") (pinfunction "A_P$3") (pintype "passive"))
      (node (ref "P_GREEN") (pin "P$3") (pinfunction "A_P$3") (pintype "passive"))
      (node (ref "P_MODA") (pin "P$3") (pinfunction "A_P$3") (pintype "passive"))
      (node (ref "P_MODB") (pin "P$3") (pinfunction "A_P$3") (pintype "passive"))
      (node (ref "P_RED") (pin "P$3") (pinfunction "A_P$3") (pintype "passive"))
      (node (ref "P_SAMPLE") (pin "P$3") (pinfunction "A_P$3") (pintype "passive"))
      (node (ref "P_X") (pin "P$3") (pinfunction "A_P$3") (pintype "passive"))
      (node (ref "P_Y") (pin "P$3") (pinfunction "A_P$3") (pintype "passive"))
      (node (ref "Q1") (pin "E") (pinfunction "E_E") (pintype "passive"))
      (node (ref "Q2") (pin "E") (pinfunction "E_E") (pintype "passive"))
      (node (ref "Q3") (pin "E") (pinfunction "E_E") (pintype "passive"))
      (node (ref "R22") (pin "1") (pinfunction "1_1") (pintype "passive"))
      (node (ref "R23") (pin "1") (pinfunction "1_1") (pintype "passive"))
      (node (ref "R25") (pin "1") (pinfunction "1_1") (pintype "passive"))
      (node (ref "SW7") (pin "1") (pinfunction "1_1") (pintype "passive"))
      (node (ref "SW7") (pin "C") (pinfunction "COM_C") (pintype "passive"))
      (node (ref "SW_BLANK") (pin "B1") (pinfunction "P_B1") (pintype "passive"))
      (node (ref "SW_BLANK") (pin "B2") (pinfunction "P1_B2") (pintype "passive"))
      (node (ref "SW_DOWN") (pin "B1") (pinfunction "P_B1") (pintype "passive"))
      (node (ref "SW_DOWN") (pin "B2") (pinfunction "P1_B2") (pintype "passive"))
      (node (ref "SW_LEFT") (pin "B1") (pinfunction "P_B1") (pintype "passive"))
      (node (ref "SW_LEFT") (pin "B2") (pinfunction "P1_B2") (pintype "passive"))
      (node (ref "SW_PLAY") (pin "B1") (pinfunction "P_B1") (pintype "passive"))
      (node (ref "SW_PLAY") (pin "B2") (pinfunction "P1_B2") (pintype "passive"))
      (node (ref "SW_RECORD") (pin "B1") (pinfunction "P_B1") (pintype "passive"))
      (node (ref "SW_RECORD") (pin "B2") (pinfunction "P1_B2") (pintype "passive"))
      (node (ref "SW_RIGHT") (pin "B1") (pinfunction "P_B1") (pintype "passive"))
      (node (ref "SW_RIGHT") (pin "B2") (pinfunction "P1_B2") (pintype "passive"))
      (node (ref "SW_UP") (pin "B1") (pinfunction "P_B1") (pintype "passive"))
      (node (ref "SW_UP") (pin "B2") (pinfunction "P1_B2") (pintype "passive"))
      (node (ref "U$3") (pin "1") (pinfunction "GND_1") (pintype "power_in"))
      (node (ref "VR1") (pin "A1") (pinfunction "CCW_1_A1") (pintype "bidirectional"))
      (node (ref "VR1") (pin "B1") (pinfunction "CCW_2_B1") (pintype "bidirectional"))
      (node (ref "VR1") (pin "MH1") (pinfunction "MH1_MH1") (pintype "bidirectional"))
      (node (ref "VR1") (pin "MH2") (pinfunction "MH2_MH2") (pintype "bidirectional"))
      (node (ref "X1") (pin "18") (pinfunction "18_18") (pintype "passive"))
      (node (ref "X1") (pin "19") (pinfunction "19_19") (pintype "passive"))
      (node (ref "X1") (pin "20") (pinfunction "20_20") (pintype "passive"))
      (node (ref "X1") (pin "25") (pinfunction "25_25") (pintype "passive"))
      (node (ref "X_IN") (pin "P1") (pinfunction "1_P1") (pintype "passive"))
      (node (ref "Y_IN") (pin "P1") (pinfunction "1_P1") (pintype "passive"))
    )
    (net (code "17") (name "INGND1") (class "Default")
      (node (ref "J2") (pin "1") (pinfunction "1_1") (pintype "passive"))
    )
    (net (code "18") (name "INGND2") (class "Default")
      (node (ref "J2") (pin "2") (pinfunction "2_2") (pintype "passive"))
    )
    (net (code "19") (name "INH1") (class "Default")
      (node (ref "IC9") (pin "6") (pinfunction "INH_6") (pintype "input"))
      (node (ref "U$2") (pin "31-CTX3") (pinfunction "31-CTX3_31-CTX3") (pintype "bidirectional"))
    )
    (net (code "20") (name "INH2") (class "Default")
      (node (ref "IC1") (pin "6") (pinfunction "INH_6") (pintype "input"))
      (node (ref "U$2") (pin "28-RX7") (pinfunction "28-RX7_28-RX7") (pintype "bidirectional"))
    )
    (net (code "21") (name "INL") (class "Default")
      (node (ref "J1") (pin "1") (pinfunction "1_1") (pintype "passive"))
    )
    (net (code "22") (name "INR") (class "Default")
      (node (ref "J1") (pin "2") (pinfunction "2_2") (pintype "passive"))
    )
    (net (code "23") (name "INTENS{slash}BLANK+") (class "Default")
      (node (ref "X1") (pin "3") (pinfunction "3_3") (pintype "passive"))
    )
    (net (code "24") (name "INTENS{slash}BLANK-") (class "Default")
      (node (ref "X1") (pin "16") (pinfunction "16_16") (pintype "passive"))
    )
    (net (code "25") (name "INTERLOCK") (class "Default")
      (node (ref "JP2") (pin "3") (pinfunction "3_3") (pintype "passive"))
      (node (ref "X1") (pin "4") (pinfunction "4_4") (pintype "passive"))
    )
    (net (code "26") (name "INTERLOCK2") (class "Default")
      (node (ref "JP2") (pin "2") (pinfunction "2_2") (pintype "passive"))
      (node (ref "X1") (pin "17") (pinfunction "17_17") (pintype "passive"))
    )
    (net (code "27") (name "LRCLK1") (class "Default")
      (node (ref "U$2") (pin "20-A6/TX5/LRCLK1") (pinfunction "20-A6/TX5/LRCLK1_20-A6/TX5/LRCLK1") (pintype "bidirectional"))
    )
    (net (code "28") (name "MCLK1") (class "Default")
      (node (ref "U$2") (pin "23-A9/CRX1/MCLK1") (pinfunction "23-A9/CRX1/MCLK1_23-A9/CRX1/MCLK1") (pintype "bidirectional"))
    )
    (net (code "29") (name "MISO") (class "Default")
      (node (ref "U$2") (pin "12-MISO/MQSL") (pinfunction "12-MISO/MQSL_12-MISO/MQSL") (pintype "bidirectional"))
    )
    (net (code "30") (name "MOD_A") (class "Default")
      (node (ref "C14") (pin "2") (pinfunction "2_2") (pintype "passive"))
      (node (ref "IC8") (pin "1") (pinfunction "OUT_1") (pintype "output"))
      (node (ref "R37") (pin "1") (pinfunction "1_1") (pintype "passive"))
      (node (ref "U$2") (pin "14-A0/TX3/SPDIF_OUT") (pinfunction "14-A0/TX3/SPDIF_OUT_14-A0/TX3/SPDIF_OUT") (pintype "bidirectional"))
    )
    (net (code "31") (name "MOD_B") (class "Default")
      (node (ref "C16") (pin "2") (pinfunction "2_2") (pintype "passive"))
      (node (ref "IC8") (pin "7") (pinfunction "OUT_7") (pintype "output"))
      (node (ref "R40") (pin "1") (pinfunction "1_1") (pintype "passive"))
      (node (ref "U$2") (pin "15-A1/RX3/SPDIF_IN") (pinfunction "15-A1/RX3/SPDIF_IN_15-A1/RX3/SPDIF_IN") (pintype "bidirectional"))
    )
    (net (code "32") (name "MOSI") (class "Default")
      (node (ref "IC7") (pin "5") (pinfunction "SDI_5") (pintype "bidirectional"))
      (node (ref "U$2") (pin "11-MOSI/CTX1") (pinfunction "11-MOSI/CTX1_11-MOSI/CTX1") (pintype "bidirectional"))
    )
    (net (code "33") (name "MUXA") (class "Default")
      (node (ref "IC1") (pin "11") (pinfunction "A_11") (pintype "input"))
      (node (ref "IC9") (pin "11") (pinfunction "A_11") (pintype "input"))
      (node (ref "U$2") (pin "29-TX7") (pinfunction "29-TX7_29-TX7") (pintype "bidirectional"))
    )
    (net (code "34") (name "MUXB") (class "Default")
      (node (ref "IC1") (pin "10") (pinfunction "B_10") (pintype "input"))
      (node (ref "IC9") (pin "10") (pinfunction "B_10") (pintype "input"))
      (node (ref "U$2") (pin "34-RX8") (pinfunction "34-RX8_34-RX8") (pintype "bidirectional"))
    )
    (net (code "35") (name "MUXC") (class "Default")
      (node (ref "IC1") (pin "9") (pinfunction "C_9") (pintype "input"))
      (node (ref "IC9") (pin "9") (pinfunction "C_9") (pintype "input"))
      (node (ref "U$2") (pin "35-TX8") (pinfunction "35/TX8_35-TX8") (pintype "bidirectional"))
    )
    (net (code "36") (name "MUXOUT1") (class "Default")
      (node (ref "IC9") (pin "3") (pinfunction "X_3") (pintype "bidirectional"))
      (node (ref "U$2") (pin "24-A10/TX6/SCL2") (pinfunction "24-A10/TX6/SCL2_24-A10/TX6/SCL2") (pintype "bidirectional"))
    )
    (net (code "37") (name "MUXOUT2") (class "Default")
      (node (ref "IC1") (pin "3") (pinfunction "X_3") (pintype "bidirectional"))
      (node (ref "U$2") (pin "25-A11/RX6/SDA2") (pinfunction "25-A11/RX6/SDA2_25-A11/RX6/SDA2") (pintype "bidirectional"))
    )
    (net (code "38") (name "Net-(IC1A-X0)") (class "Default")
      (node (ref "IC1") (pin "13") (pinfunction "X0_13") (pintype "bidirectional"))
      (node (ref "SW7") (pin "2") (pinfunction "2_2") (pintype "passive"))
    )
    (net (code "39") (name "Net-(IC1A-X1)") (class "Default")
      (node (ref "IC1") (pin "14") (pinfunction "X1_14") (pintype "bidirectional"))
      (node (ref "SW_RECORD") (pin "A2") (pinfunction "S1_A2") (pintype "passive"))
    )
    (net (code "40") (name "Net-(IC1A-X2)") (class "Default")
      (node (ref "IC1") (pin "15") (pinfunction "X2_15") (pintype "bidirectional"))
      (node (ref "SW_BLANK") (pin "A2") (pinfunction "S1_A2") (pintype "passive"))
    )
    (net (code "41") (name "Net-(IC1A-X3)") (class "Default")
      (node (ref "IC1") (pin "12") (pinfunction "X3_12") (pintype "bidirectional"))
      (node (ref "SW_PLAY") (pin "A2") (pinfunction "S1_A2") (pintype "passive"))
    )
    (net (code "42") (name "Net-(IC1A-X4)") (class "Default")
      (node (ref "IC1") (pin "1") (pinfunction "X4_1") (pintype "bidirectional"))
      (node (ref "SW_RIGHT") (pin "A2") (pinfunction "S1_A2") (pintype "passive"))
    )
    (net (code "43") (name "Net-(IC1A-X5)") (class "Default")
      (node (ref "IC1") (pin "5") (pinfunction "X5_5") (pintype "bidirectional"))
      (node (ref "SW_LEFT") (pin "A2") (pinfunction "S1_A2") (pintype "passive"))
    )
    (net (code "44") (name "Net-(IC1A-X6)") (class "Default")
      (node (ref "IC1") (pin "2") (pinfunction "X6_2") (pintype "bidirectional"))
      (node (ref "SW_DOWN") (pin "A2") (pinfunction "S1_A2") (pintype "passive"))
    )
    (net (code "45") (name "Net-(IC1A-X7)") (class "Default")
      (node (ref "IC1") (pin "4") (pinfunction "X7_4") (pintype "bidirectional"))
      (node (ref "SW_UP") (pin "A2") (pinfunction "S1_A2") (pintype "passive"))
    )
    (net (code "46") (name "Net-(IC2-VIN)") (class "Default")
      (node (ref "C12") (pin "+") (pinfunction "+_+") (pintype "passive"))
      (node (ref "IC2") (pin "2") (pinfunction "VIN_2") (pintype "input"))
      (node (ref "R7") (pin "1") (pinfunction "1_1") (pintype "passive"))
    )
    (net (code "47") (name "Net-(IC4A--IN)") (class "Default")
      (node (ref "IC4") (pin "2") (pinfunction "-IN_2") (pintype "input"))
      (node (ref "R30") (pin "1") (pinfunction "1_1") (pintype "passive"))
      (node (ref "R31") (pin "2") (pinfunction "2_2") (pintype "passive"))
    )
    (net (code "48") (name "Net-(IC4A-OUT)") (class "Default")
      (node (ref "IC4") (pin "1") (pinfunction "OUT_1") (pintype "output"))
      (node (ref "R16") (pin "1") (pinfunction "1_1") (pintype "passive"))
      (node (ref "R30") (pin "2") (pinfunction "2_2") (pintype "passive"))
    )
    (net (code "49") (name "Net-(IC4B--IN)") (class "Default")
      (node (ref "IC4") (pin "6") (pinfunction "-IN_6") (pintype "input"))
      (node (ref "IC4") (pin "7") (pinfunction "OUT_7") (pintype "output"))
      (node (ref "R35") (pin "1") (pinfunction "1_1") (pintype "passive"))
    )
    (net (code "50") (name "Net-(IC4C--IN)") (class "Default")
      (node (ref "IC4") (pin "9") (pinfunction "-IN_9") (pintype "input"))
      (node (ref "R32") (pin "1") (pinfunction "1_1") (pintype "passive"))
      (node (ref "R33") (pin "2") (pinfunction "2_2") (pintype "passive"))
    )
    (net (code "51") (name "Net-(IC4C-OUT)") (class "Default")
      (node (ref "IC4") (pin "8") (pinfunction "OUT_8") (pintype "output"))
      (node (ref "R24") (pin "1") (pinfunction "1_1") (pintype "passive"))
      (node (ref "R32") (pin "2") (pinfunction "2_2") (pintype "passive"))
    )
    (net (code "52") (name "Net-(IC4D--IN)") (class "Default")
      (node (ref "IC4") (pin "13") (pinfunction "-IN_13") (pintype "input"))
      (node (ref "IC4") (pin "14") (pinfunction "OUT_14") (pintype "output"))
      (node (ref "R21") (pin "1") (pinfunction "1_1") (pintype "passive"))
    )
    (net (code "53") (name "Net-(IC6A--IN)") (class "Default")
      (node (ref "C15") (pin "1") (pinfunction "1_1") (pintype "passive"))
      (node (ref "IC6") (pin "2") (pinfunction "-IN_2") (pintype "input"))
      (node (ref "R10") (pin "1") (pinfunction "1_1") (pintype "passive"))
      (node (ref "R8") (pin "1") (pinfunction "1_1") (pintype "passive"))
      (node (ref "R9") (pin "2") (pinfunction "2_2") (pintype "passive"))
    )
    (net (code "54") (name "Net-(IC6B--IN)") (class "Default")
      (node (ref "C13") (pin "1") (pinfunction "1_1") (pintype "passive"))
      (node (ref "IC6") (pin "6") (pinfunction "-IN_6") (pintype "input"))
      (node (ref "R11") (pin "1") (pinfunction "1_1") (pintype "passive"))
      (node (ref "R13") (pin "2") (pinfunction "2_2") (pintype "passive"))
      (node (ref "R14") (pin "1") (pinfunction "1_1") (pintype "passive"))
    )
    (net (code "55") (name "Net-(IC7-VOUTA)") (class "Default")
      (node (ref "IC7") (pin "14") (pinfunction "VOUTA_14") (pintype "bidirectional"))
      (node (ref "JP5") (pin "2") (pinfunction "2_2") (pintype "passive"))
    )
    (net (code "56") (name "Net-(IC7-VOUTB)") (class "Default")
      (node (ref "IC7") (pin "10") (pinfunction "VOUTB_10") (pintype "bidirectional"))
      (node (ref "JP4") (pin "1") (pinfunction "1_1") (pintype "passive"))
    )
    (net (code "57") (name "Net-(IC8A--IN)") (class "Default")
      (node (ref "C14") (pin "1") (pinfunction "1_1") (pintype "passive"))
      (node (ref "IC8") (pin "2") (pinfunction "-IN_2") (pintype "input"))
      (node (ref "R36") (pin "1") (pinfunction "1_1") (pintype "passive"))
      (node (ref "R37") (pin "2") (pinfunction "2_2") (pintype "passive"))
      (node (ref "R38") (pin "1") (pinfunction "1_1") (pintype "passive"))
    )
    (net (code "58") (name "Net-(IC8B--IN)") (class "Default")
      (node (ref "C16") (pin "1") (pinfunction "1_1") (pintype "passive"))
      (node (ref "IC8") (pin "6") (pinfunction "-IN_6") (pintype "input"))
      (node (ref "R39") (pin "1") (pinfunction "1_1") (pintype "passive"))
      (node (ref "R40") (pin "2") (pinfunction "2_2") (pintype "passive"))
      (node (ref "R41") (pin "1") (pinfunction "1_1") (pintype "passive"))
    )
    (net (code "59") (name "Net-(IC9A-X0)") (class "Default")
      (node (ref "IC9") (pin "13") (pinfunction "X0_13") (pintype "bidirectional"))
      (node (ref "P_RED") (pin "P$2") (pinfunction "S_P$2") (pintype "passive"))
    )
    (net (code "60") (name "Net-(IC9A-X1)") (class "Default")
      (node (ref "IC9") (pin "14") (pinfunction "X1_14") (pintype "bidirectional"))
      (node (ref "P_BLUE") (pin "P$2") (pinfunction "S_P$2") (pintype "passive"))
    )
    (net (code "61") (name "Net-(IC9A-X2)") (class "Default")
      (node (ref "IC9") (pin "15") (pinfunction "X2_15") (pintype "bidirectional"))
      (node (ref "P_GREEN") (pin "P$2") (pinfunction "S_P$2") (pintype "passive"))
    )
    (net (code "62") (name "Net-(IC9A-X3)") (class "Default")
      (node (ref "IC9") (pin "12") (pinfunction "X3_12") (pintype "bidirectional"))
      (node (ref "P_X") (pin "P$2") (pinfunction "S_P$2") (pintype "passive"))
    )
    (net (code "63") (name "Net-(IC9A-X4)") (class "Default")
      (node (ref "IC9") (pin "1") (pinfunction "X4_1") (pintype "bidirectional"))
      (node (ref "P_Y") (pin "P$2") (pinfunction "S_P$2") (pintype "passive"))
    )
    (net (code "64") (name "Net-(IC9A-X5)") (class "Default")
      (node (ref "IC9") (pin "5") (pinfunction "X5_5") (pintype "bidirectional"))
      (node (ref "P_MODA") (pin "P$2") (pinfunction "S_P$2") (pintype "passive"))
    )
    (net (code "65") (name "Net-(IC9A-X6)") (class "Default")
      (node (ref "IC9") (pin "2") (pinfunction "X6_2") (pintype "bidirectional"))
      (node (ref "P_MODB") (pin "P$2") (pinfunction "S_P$2") (pintype "passive"))
    )
    (net (code "66") (name "Net-(IC9A-X7)") (class "Default")
      (node (ref "IC9") (pin "4") (pinfunction "X7_4") (pintype "bidirectional"))
      (node (ref "P_SAMPLE") (pin "P$2") (pinfunction "S_P$2") (pintype "passive"))
    )
    (net (code "67") (name "Net-(IC10C--IN)") (class "Default")
      (node (ref "IC10") (pin "8") (pinfunction "OUT_8") (pintype "output"))
      (node (ref "IC10") (pin "9") (pinfunction "-IN_9") (pintype "input"))
      (node (ref "R18") (pin "1") (pinfunction "1_1") (pintype "passive"))
    )
    (net (code "68") (name "Net-(IC10D--IN)") (class "Default")
      (node (ref "IC10") (pin "13") (pinfunction "-IN_13") (pintype "input"))
      (node (ref "IC10") (pin "14") (pinfunction "OUT_14") (pintype "output"))
    )
    (net (code "69") (name "Net-(JP1-Pad1)") (class "Default")
      (node (ref "JP1") (pin "1") (pinfunction "1_1") (pintype "passive"))
      (node (ref "JP1") (pin "2") (pinfunction "2_2") (pintype "passive"))
      (node (ref "P2") (pin "2") (pinfunction "2_2") (pintype "bidirectional"))
    )
    (net (code "70") (name "Net-(JP1-Pad10)") (class "Default")
      (node (ref "JP1") (pin "10") (pinfunction "10_10") (pintype "passive"))
      (node (ref "JP1") (pin "9") (pinfunction "9_9") (pintype "passive"))
      (node (ref "P1") (pin "2") (pinfunction "2_2") (pintype "bidirectional"))
    )
    (net (code "71") (name "Net-(JP1-Pad11)") (class "Default")
      (node (ref "JP1") (pin "11") (pinfunction "11_11") (pintype "passive"))
      (node (ref "JP1") (pin "12") (pinfunction "12_12") (pintype "passive"))
      (node (ref "P3") (pin "2") (pinfunction "2_2") (pintype "bidirectional"))
    )
    (net (code "72") (name "Net-(J_BLUE-3)") (class "Default")
      (node (ref "J_BLUE") (pin "P3") (pinfunction "3_P3") (pintype "passive"))
      (node (ref "R46") (pin "1") (pinfunction "1_1") (pintype "passive"))
    )
    (net (code "73") (name "Net-(J_GREEN-3)") (class "Default")
      (node (ref "J_GREEN") (pin "P3") (pinfunction "3_P3") (pintype "passive"))
      (node (ref "R44") (pin "1") (pinfunction "1_1") (pintype "passive"))
    )
    (net (code "74") (name "Net-(J_RED-3)") (class "Default")
      (node (ref "J_RED") (pin "P3") (pinfunction "3_P3") (pintype "passive"))
      (node (ref "R42") (pin "1") (pinfunction "1_1") (pintype "passive"))
    )
    (net (code "75") (name "Net-(MOD_A-3)") (class "Default")
      (node (ref "MOD_A") (pin "P3") (pinfunction "3_P3") (pintype "passive"))
      (node (ref "R36") (pin "2") (pinfunction "2_2") (pintype "passive"))
    )
    (net (code "76") (name "Net-(MOD_B-3)") (class "Default")
      (node (ref "MOD_B") (pin "P3") (pinfunction "3_P3") (pintype "passive"))
      (node (ref "R39") (pin "2") (pinfunction "2_2") (pintype "passive"))
    )
    (net (code "77") (name "Net-(Q1-PadB)") (class "Default")
      (node (ref "Q1") (pin "B") (pinfunction "B_B") (pintype "passive"))
      (node (ref "R44") (pin "2") (pinfunction "2_2") (pintype "passive"))
    )
    (net (code "78") (name "Net-(Q2-PadB)") (class "Default")
      (node (ref "Q2") (pin "B") (pinfunction "B_B") (pintype "passive"))
      (node (ref "R42") (pin "2") (pinfunction "2_2") (pintype "passive"))
    )
    (net (code "79") (name "Net-(Q3-PadB)") (class "Default")
      (node (ref "Q3") (pin "B") (pinfunction "B_B") (pintype "passive"))
      (node (ref "R46") (pin "2") (pinfunction "2_2") (pintype "passive"))
    )
    (net (code "80") (name "Net-(U$2-5V)") (class "Default")
      (node (ref "U$2") (pin "+5V") (pinfunction "5V_+5V") (pintype "bidirectional"))
      (node (ref "X2") (pin "1") (pinfunction "1_1") (pintype "passive"))
    )
    (net (code "81") (name "Net-(U$2-PadDM)") (class "Default")
      (node (ref "U$2") (pin "DM") (pinfunction "DM_DM") (pintype "bidirectional"))
      (node (ref "X2") (pin "2") (pinfunction "2_2") (pintype "passive"))
    )
    (net (code "82") (name "Net-(U$2-PadDP)") (class "Default")
      (node (ref "U$2") (pin "DP") (pinfunction "DP_DP") (pintype "bidirectional"))
      (node (ref "X2") (pin "3") (pinfunction "3_3") (pintype "passive"))
    )
    (net (code "83") (name "Net-(U$2-PadGND4)") (class "Default")
      (node (ref "U$2") (pin "GND4") (pinfunction "GND4_GND4") (pintype "bidirectional"))
      (node (ref "X2") (pin "4") (pinfunction "4_4") (pintype "passive"))
    )
    (net (code "84") (name "Net-(U1A--IN)") (class "Default")
      (node (ref "R26") (pin "2") (pinfunction "2_2") (pintype "passive"))
      (node (ref "R27") (pin "1") (pinfunction "1_1") (pintype "passive"))
      (node (ref "U1") (pin "2") (pinfunction "-IN_2") (pintype "input"))
    )
    (net (code "85") (name "Net-(U1B--IN)") (class "Default")
      (node (ref "R28") (pin "2") (pinfunction "2_2") (pintype "passive"))
      (node (ref "R29") (pin "1") (pinfunction "1_1") (pintype "passive"))
      (node (ref "U1") (pin "6") (pinfunction "-IN_6") (pintype "input"))
    )
    (net (code "86") (name "Net-(VR1-CW_1)") (class "Default")
      (node (ref "R11") (pin "2") (pinfunction "2_2") (pintype "passive"))
      (node (ref "VR1") (pin "A3") (pinfunction "CW_1_A3") (pintype "bidirectional"))
    )
    (net (code "87") (name "Net-(VR1-CW_2)") (class "Default")
      (node (ref "R8") (pin "2") (pinfunction "2_2") (pintype "passive"))
      (node (ref "VR1") (pin "B3") (pinfunction "CW_2_B3") (pintype "bidirectional"))
    )
    (net (code "88") (name "Net-(VR1-WIPER_1)") (class "Default")
      (node (ref "VR1") (pin "A2") (pinfunction "WIPER_1_A2") (pintype "bidirectional"))
      (node (ref "Y_IN") (pin "P3") (pinfunction "3_P3") (pintype "passive"))
    )
    (net (code "89") (name "Net-(VR1-WIPER_2)") (class "Default")
      (node (ref "VR1") (pin "B2") (pinfunction "WIPER_2_B2") (pintype "bidirectional"))
      (node (ref "X_IN") (pin "P3") (pinfunction "3_P3") (pintype "passive"))
    )
    (net (code "90") (name "OUTGND") (class "Default")
      (node (ref "J1") (pin "4") (pinfunction "4_4") (pintype "passive"))
    )
    (net (code "91") (name "OUTL") (class "Default")
      (node (ref "J1") (pin "5") (pinfunction "5_5") (pintype "passive"))
      (node (ref "JP5") (pin "1") (pinfunction "1_1") (pintype "passive"))
      (node (ref "U1") (pin "3") (pinfunction "+IN_3") (pintype "input"))
    )
    (net (code "92") (name "OUTR") (class "Default")
      (node (ref "J1") (pin "3") (pinfunction "3_3") (pintype "passive"))
      (node (ref "JP4") (pin "2") (pinfunction "2_2") (pintype "passive"))
      (node (ref "U1") (pin "5") (pinfunction "+IN_5") (pintype "input"))
    )
    (net (code "93") (name "R+") (class "Default")
      (node (ref "R20") (pin "2") (pinfunction "2_2") (pintype "passive"))
      (node (ref "X1") (pin "5") (pinfunction "5_5") (pintype "passive"))
    )
    (net (code "94") (name "R1+") (class "Default")
      (node (ref "IC10") (pin "1") (pinfunction "OUT_1") (pintype "output"))
      (node (ref "IC10") (pin "2") (pinfunction "-IN_2") (pintype "input"))
      (node (ref "R20") (pin "1") (pinfunction "1_1") (pintype "passive"))
    )
    (net (code "95") (name "RX_DOUT") (class "Default")
      (node (ref "U$2") (pin "8-TX2/IN1") (pinfunction "8-TX2/IN1_8-TX2/IN1") (pintype "bidirectional"))
    )
    (net (code "96") (name "SCK") (class "Default")
      (node (ref "IC7") (pin "4") (pinfunction "SCK_4") (pintype "bidirectional"))
      (node (ref "U$2") (pin "13-SCK/LED") (pinfunction "13-SCK/LED_13-SCK/LED") (pintype "bidirectional"))
    )
    (net (code "97") (name "SCL") (class "Default")
      (node (ref "U$2") (pin "19-A5/SCL0") (pinfunction "19-A5/SCL0_19-A5/SCL0") (pintype "bidirectional"))
      (node (ref "U$3") (pin "3") (pinfunction "SCL_3") (pintype "bidirectional"))
    )
    (net (code "98") (name "SDA") (class "Default")
      (node (ref "U$2") (pin "18-A4/SDA0") (pinfunction "18-A4/SDA0_18-A4/SDA0") (pintype "bidirectional"))
      (node (ref "U$3") (pin "4") (pinfunction "SDA_4") (pintype "bidirectional"))
    )
    (net (code "99") (name "SHUTTER") (class "Default")
      (node (ref "U$2") (pin "30-CRX3") (pinfunction "30-CRX3_30-CRX3") (pintype "bidirectional"))
      (node (ref "X1") (pin "13") (pinfunction "13_13") (pintype "passive"))
    )
    (net (code "100") (name "SS") (class "Default")
      (node (ref "IC7") (pin "3") (pinfunction "~{CS}_3") (pintype "bidirectional"))
      (node (ref "U$2") (pin "10-CS\\MQSR") (pinfunction "10-CS/MQSR_10-CS\\MQSR") (pintype "bidirectional"))
    )
    (net (code "101") (name "T26") (class "Default")
      (node (ref "Q2") (pin "C") (pinfunction "C_C") (pintype "passive"))
      (node (ref "R43") (pin "1") (pinfunction "1_1") (pintype "passive"))
      (node (ref "U$2") (pin "26-A12/MOSI1") (pinfunction "26-A12/MOSI1_26-A12/MOSI1") (pintype "bidirectional"))
    )
    (net (code "102") (name "T27") (class "Default")
      (node (ref "Q1") (pin "C") (pinfunction "C_C") (pintype "passive"))
      (node (ref "R45") (pin "1") (pinfunction "1_1") (pintype "passive"))
      (node (ref "U$2") (pin "27-A13/SCK1") (pinfunction "27-A13/SCK1_27-A13/SCK1") (pintype "bidirectional"))
    )
    (net (code "103") (name "T38") (class "Default")
      (node (ref "Q3") (pin "C") (pinfunction "C_C") (pintype "passive"))
      (node (ref "R47") (pin "1") (pinfunction "1_1") (pintype "passive"))
      (node (ref "U$2") (pin "38-A14/CS/IN1") (pinfunction "38-A14/CS/IN1_38-A14/CS/IN1") (pintype "bidirectional"))
    )
    (net (code "104") (name "T39") (class "Default")
      (node (ref "U$2") (pin "39-A15/CS/OUT1A") (pinfunction "39-A15/CS/OUT1A_39-A15/CS/OUT1A") (pintype "bidirectional"))
    )
    (net (code "105") (name "TB") (class "Default")
      (node (ref "IC10") (pin "10") (pinfunction "+IN_10") (pintype "input"))
      (node (ref "R22") (pin "2") (pinfunction "2_2") (pintype "passive"))
      (node (ref "U$2") (pin "2-OUT2") (pinfunction "2-OUT2_2-OUT2") (pintype "bidirectional"))
    )
    (net (code "106") (name "TG") (class "Default")
      (node (ref "IC10") (pin "5") (pinfunction "+IN_5") (pintype "input"))
      (node (ref "R23") (pin "2") (pinfunction "2_2") (pintype "passive"))
      (node (ref "U$2") (pin "9-OUT1C") (pinfunction "9-OUT1C_9-OUT1C") (pintype "bidirectional"))
    )
    (net (code "107") (name "TR") (class "Default")
      (node (ref "IC10") (pin "3") (pinfunction "+IN_3") (pintype "input"))
      (node (ref "R25") (pin "2") (pinfunction "2_2") (pintype "passive"))
      (node (ref "U$2") (pin "32-OUT1B") (pinfunction "32-OUT1B_32-OUT1B") (pintype "bidirectional"))
    )
    (net (code "108") (name "TX_DIN") (class "Default")
      (node (ref "U$2") (pin "7-RX2/OUT1A") (pinfunction "7-RX2/OUT1A_7-RX2/OUT1A") (pintype "bidirectional"))
    )
    (net (code "109") (name "X+") (class "Default")
      (node (ref "R35") (pin "2") (pinfunction "2_2") (pintype "passive"))
      (node (ref "X1") (pin "1") (pinfunction "1_1") (pintype "passive"))
    )
    (net (code "110") (name "X-") (class "Default")
      (node (ref "R24") (pin "2") (pinfunction "2_2") (pintype "passive"))
      (node (ref "X1") (pin "14") (pinfunction "14_14") (pintype "passive"))
    )
    (net (code "111") (name "X2") (class "Default")
      (node (ref "IC4") (pin "5") (pinfunction "+IN_5") (pintype "input"))
      (node (ref "R27") (pin "2") (pinfunction "2_2") (pintype "passive"))
      (node (ref "R33") (pin "1") (pinfunction "1_1") (pintype "passive"))
      (node (ref "U1") (pin "1") (pinfunction "OUT_1") (pintype "output"))
    )
    (net (code "112") (name "X_IN") (class "Default")
      (node (ref "C15") (pin "2") (pinfunction "2_2") (pintype "passive"))
      (node (ref "IC6") (pin "1") (pinfunction "OUT_1") (pintype "output"))
      (node (ref "R9") (pin "1") (pinfunction "1_1") (pintype "passive"))
      (node (ref "U$2") (pin "17-A3/TX4/SDA1") (pinfunction "17-A3/TX4/SDA1_17-A3/TX4/SDA1") (pintype "bidirectional"))
    )
    (net (code "113") (name "Y+") (class "Default")
      (node (ref "R21") (pin "2") (pinfunction "2_2") (pintype "passive"))
      (node (ref "X1") (pin "2") (pinfunction "2_2") (pintype "passive"))
    )
    (net (code "114") (name "Y-") (class "Default")
      (node (ref "R16") (pin "2") (pinfunction "2_2") (pintype "passive"))
      (node (ref "X1") (pin "15") (pinfunction "15_15") (pintype "passive"))
    )
    (net (code "115") (name "Y2") (class "Default")
      (node (ref "IC4") (pin "12") (pinfunction "+IN_12") (pintype "input"))
      (node (ref "R29") (pin "2") (pinfunction "2_2") (pintype "passive"))
      (node (ref "R31") (pin "1") (pinfunction "1_1") (pintype "passive"))
      (node (ref "U1") (pin "7") (pinfunction "OUT_7") (pintype "output"))
    )
    (net (code "116") (name "Y_IN") (class "Default")
      (node (ref "C13") (pin "2") (pinfunction "2_2") (pintype "passive"))
      (node (ref "IC6") (pin "7") (pinfunction "OUT_7") (pintype "output"))
      (node (ref "R13") (pin "1") (pinfunction "1_1") (pintype "passive"))
      (node (ref "U$2") (pin "16-A2/RX4/SCL1") (pinfunction "16-A2/RX4/SCL1_16-A2/RX4/SCL1") (pintype "bidirectional"))
    )
    (net (code "117") (name "unconnected-(IC7-NC_1-Pad2)") (class "Default")
      (node (ref "IC7") (pin "2") (pinfunction "NC_1_2") (pintype "bidirectional"))
    )
    (net (code "118") (name "unconnected-(IC7-NC_2-Pad6)") (class "Default")
      (node (ref "IC7") (pin "6") (pinfunction "NC_2_6") (pintype "bidirectional"))
    )
    (net (code "119") (name "unconnected-(IC7-NC_3-Pad7)") (class "Default")
      (node (ref "IC7") (pin "7") (pinfunction "NC_3_7") (pintype "bidirectional"))
    )
    (net (code "120") (name "unconnected-(JP1-Pad13)") (class "Default")
      (node (ref "JP1") (pin "13") (pinfunction "13_13") (pintype "passive"))
    )
    (net (code "121") (name "unconnected-(JP1-Pad14)") (class "Default")
      (node (ref "JP1") (pin "14") (pinfunction "14_14") (pintype "passive"))
    )
    (net (code "122") (name "unconnected-(JP1-Pad15)") (class "Default")
      (node (ref "JP1") (pin "15") (pinfunction "15_15") (pintype "passive"))
    )
    (net (code "123") (name "unconnected-(JP1-Pad16)") (class "Default")
      (node (ref "JP1") (pin "16") (pinfunction "16_16") (pintype "passive"))
    )
    (net (code "124") (name "unconnected-(JP2-Pad1)") (class "Default")
      (node (ref "JP2") (pin "1") (pinfunction "1_1") (pintype "passive"))
    )
    (net (code "125") (name "unconnected-(SW_BLANK-S-PadA1)") (class "Default")
      (node (ref "SW_BLANK") (pin "A1") (pinfunction "S_A1") (pintype "passive"))
    )
    (net (code "126") (name "unconnected-(SW_DOWN-S-PadA1)") (class "Default")
      (node (ref "SW_DOWN") (pin "A1") (pinfunction "S_A1") (pintype "passive"))
    )
    (net (code "127") (name "unconnected-(SW_LEFT-S-PadA1)") (class "Default")
      (node (ref "SW_LEFT") (pin "A1") (pinfunction "S_A1") (pintype "passive"))
    )
    (net (code "128") (name "unconnected-(SW_PLAY-S-PadA1)") (class "Default")
      (node (ref "SW_PLAY") (pin "A1") (pinfunction "S_A1") (pintype "passive"))
    )
    (net (code "129") (name "unconnected-(SW_RECORD-S-PadA1)") (class "Default")
      (node (ref "SW_RECORD") (pin "A1") (pinfunction "S_A1") (pintype "passive"))
    )
    (net (code "130") (name "unconnected-(SW_RIGHT-S-PadA1)") (class "Default")
      (node (ref "SW_RIGHT") (pin "A1") (pinfunction "S_A1") (pintype "passive"))
    )
    (net (code "131") (name "unconnected-(SW_UP-S-PadA1)") (class "Default")
      (node (ref "SW_UP") (pin "A1") (pinfunction "S_A1") (pintype "passive"))
    )
    (net (code "132") (name "unconnected-(U$2-Pad0-RX1{slash}CS1{slash}CRX2)") (class "Default")
      (node (ref "U$2") (pin "0-RX1/CS1/CRX2") (pinfunction "0-RX1/CS1/CRX2_0-RX1/CS1/CRX2") (pintype "bidirectional"))
    )
    (net (code "133") (name "unconnected-(U$2-Pad1-TX1{slash}MISO1{slash}CTX2)") (class "Default")
      (node (ref "U$2") (pin "1-TX1/MISO1/CTX2") (pinfunction "1-TX1/MISO1/CTX2_1-TX1/MISO1/CTX2") (pintype "bidirectional"))
    )
    (net (code "134") (name "unconnected-(U$2-Pad3-LRCLK2)") (class "Default")
      (node (ref "U$2") (pin "3-LRCLK2") (pinfunction "3-LRCLK2_3-LRCLK2") (pintype "bidirectional"))
    )
    (net (code "135") (name "unconnected-(U$2-Pad3V3-2)") (class "Default")
      (node (ref "U$2") (pin "3V3-2") (pinfunction "3V3-2_3V3-2") (pintype "bidirectional"))
    )
    (net (code "136") (name "unconnected-(U$2-Pad3V3-3)") (class "Default")
      (node (ref "U$2") (pin "3V3-3") (pinfunction "3V3-3_3V3-3") (pintype "bidirectional"))
    )
    (net (code "137") (name "unconnected-(U$2-Pad4-BCLK2)") (class "Default")
      (node (ref "U$2") (pin "4-BCLK2") (pinfunction "4-BCLK2_4-BCLK2") (pintype "bidirectional"))
    )
    (net (code "138") (name "unconnected-(U$2-Pad5-IN2)") (class "Default")
      (node (ref "U$2") (pin "5-IN2") (pinfunction "5-IN2_5-IN2") (pintype "bidirectional"))
    )
    (net (code "139") (name "unconnected-(U$2-Pad6-OUT1D)") (class "Default")
      (node (ref "U$2") (pin "6-OUT1D") (pinfunction "6-OUT1D_6-OUT1D") (pintype "bidirectional"))
    )
    (net (code "140") (name "unconnected-(U$2-Pad33-MCLK2)") (class "Default")
      (node (ref "U$2") (pin "33-MCLK2") (pinfunction "33-MCLK2_33-MCLK2") (pintype "bidirectional"))
    )
    (net (code "141") (name "unconnected-(U$2-Pad36-PWM)") (class "Default")
      (node (ref "U$2") (pin "36-PWM") (pinfunction "36-PWM_36-PWM") (pintype "bidirectional"))
    )
    (net (code "142") (name "unconnected-(U$2-Pad37-PWM)") (class "Default")
      (node (ref "U$2") (pin "37-PWM") (pinfunction "37-PWM_37-PWM") (pintype "bidirectional"))
    )
    (net (code "143") (name "unconnected-(U$2-PadGND1)") (class "Default")
      (node (ref "U$2") (pin "GND1") (pinfunction "GND1_GND1") (pintype "bidirectional"))
    )
    (net (code "144") (name "unconnected-(U$2-PadGND2)") (class "Default")
      (node (ref "U$2") (pin "GND2") (pinfunction "GND2_GND2") (pintype "bidirectional"))
    )
    (net (code "145") (name "unconnected-(U$2-PadGND3)") (class "Default")
      (node (ref "U$2") (pin "GND3") (pinfunction "GND3_GND3") (pintype "bidirectional"))
    )
    (net (code "146") (name "unconnected-(U$2-PadGND5)") (class "Default")
      (node (ref "U$2") (pin "GND5") (pinfunction "GND5_GND5") (pintype "bidirectional"))
    )
    (net (code "147") (name "unconnected-(U$2-PadGND6)") (class "Default")
      (node (ref "U$2") (pin "GND6") (pinfunction "GND6_GND6") (pintype "bidirectional"))
    )
    (net (code "148") (name "unconnected-(U$2-PadON{slash}OFF)") (class "Default")
      (node (ref "U$2") (pin "ON/OFF") (pinfunction "ON/OFF_ON/OFF") (pintype "bidirectional"))
    )
    (net (code "149") (name "unconnected-(U$2-PadPROGRAM)") (class "Default")
      (node (ref "U$2") (pin "PROGRAM") (pinfunction "PROGRAM_PROGRAM") (pintype "bidirectional"))
    )
    (net (code "150") (name "unconnected-(U$2-PadVBAT)") (class "Default")
      (node (ref "U$2") (pin "VBAT") (pinfunction "VBAT_VBAT") (pintype "bidirectional"))
    )
    (net (code "151") (name "unconnected-(U$2-PadVUSB)") (class "Default")
      (node (ref "U$2") (pin "VUSB") (pinfunction "VUSB_VUSB") (pintype "bidirectional"))
    )
    (net (code "152") (name "unconnected-(X1-Pad8)") (class "Default")
      (node (ref "X1") (pin "8") (pinfunction "8_8") (pintype "passive"))
    )
    (net (code "153") (name "unconnected-(X1-Pad9)") (class "Default")
      (node (ref "X1") (pin "9") (pinfunction "9_9") (pintype "passive"))
    )
    (net (code "154") (name "unconnected-(X1-Pad10)") (class "Default")
      (node (ref "X1") (pin "10") (pinfunction "10_10") (pintype "passive"))
    )
    (net (code "155") (name "unconnected-(X1-Pad11)") (class "Default")
      (node (ref "X1") (pin "11") (pinfunction "11_11") (pintype "passive"))
    )
    (net (code "156") (name "unconnected-(X1-Pad12)") (class "Default")
      (node (ref "X1") (pin "12") (pinfunction "12_12") (pintype "passive"))
    )
    (net (code "157") (name "unconnected-(X1-Pad21)") (class "Default")
      (node (ref "X1") (pin "21") (pinfunction "21_21") (pintype "passive"))
    )
    (net (code "158") (name "unconnected-(X1-Pad22)") (class "Default")
      (node (ref "X1") (pin "22") (pinfunction "22_22") (pintype "passive"))
    )
    (net (code "159") (name "unconnected-(X1-Pad23)") (class "Default")
      (node (ref "X1") (pin "23") (pinfunction "23_23") (pintype "passive"))
    )
    (net (code "160") (name "unconnected-(X1-Pad24)") (class "Default")
      (node (ref "X1") (pin "24") (pinfunction "24_24") (pintype "passive"))
    )
    (net (code "161") (name "~{LDAC}") (class "Default")
      (node (ref "IC7") (pin "8") (pinfunction "~{LDAC}_8") (pintype "bidirectional"))
      (node (ref "U$2") (pin "22-A8/CTX1") (pinfunction "22-A8/CTX1_22-A8/CTX1") (pintype "bidirectional"))
    )
  )
)
